# UV-LED.net
KiCad netlist of a schematic drawn in EAGLE
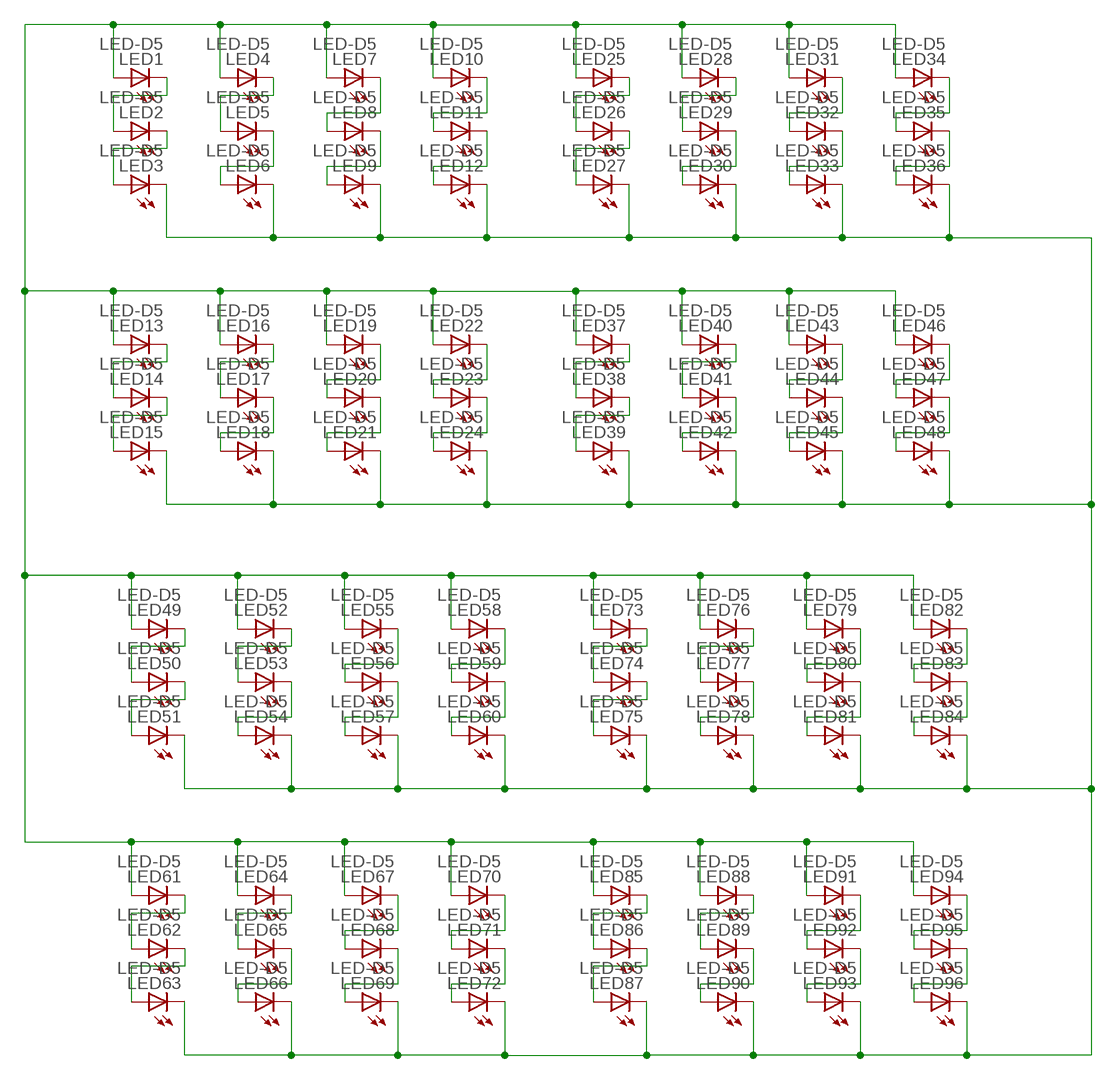
[diagram p0: schematic, sheet 1]

(export (version "E")
  (design (tool "Eeschema 10.0.6"))
  (components
    (comp (ref "LED1")
      (value "LED-D5")
      (footprint "eagle-import:LED-D5")
      (libsource (lib "eagle-import") (part "LED-D5"))
    )
    (comp (ref "LED2")
      (value "LED-D5")
      (footprint "eagle-import:LED-D5")
      (libsource (lib "eagle-import") (part "LED-D5"))
    )
    (comp (ref "LED3")
      (value "LED-D5")
      (footprint "eagle-import:LED-D5")
      (libsource (lib "eagle-import") (part "LED-D5"))
    )
    (comp (ref "LED4")
      (value "LED-D5")
      (footprint "eagle-import:LED-D5")
      (libsource (lib "eagle-import") (part "LED-D5"))
    )
    (comp (ref "LED5")
      (value "LED-D5")
      (footprint "eagle-import:LED-D5")
      (libsource (lib "eagle-import") (part "LED-D5"))
    )
    (comp (ref "LED6")
      (value "LED-D5")
      (footprint "eagle-import:LED-D5")
      (libsource (lib "eagle-import") (part "LED-D5"))
    )
    (comp (ref "LED7")
      (value "LED-D5")
      (footprint "eagle-import:LED-D5")
      (libsource (lib "eagle-import") (part "LED-D5"))
    )
    (comp (ref "LED8")
      (value "LED-D5")
      (footprint "eagle-import:LED-D5")
      (libsource (lib "eagle-import") (part "LED-D5"))
    )
    (comp (ref "LED9")
      (value "LED-D5")
      (footprint "eagle-import:LED-D5")
      (libsource (lib "eagle-import") (part "LED-D5"))
    )
    (comp (ref "LED10")
      (value "LED-D5")
      (footprint "eagle-import:LED-D5")
      (libsource (lib "eagle-import") (part "LED-D5"))
    )
    (comp (ref "LED11")
      (value "LED-D5")
      (footprint "eagle-import:LED-D5")
      (libsource (lib "eagle-import") (part "LED-D5"))
    )
    (comp (ref "LED12")
      (value "LED-D5")
      (footprint "eagle-import:LED-D5")
      (libsource (lib "eagle-import") (part "LED-D5"))
    )
    (comp (ref "LED13")
      (value "LED-D5")
      (footprint "eagle-import:LED-D5")
      (libsource (lib "eagle-import") (part "LED-D5"))
    )
    (comp (ref "LED14")
      (value "LED-D5")
      (footprint "eagle-import:LED-D5")
      (libsource (lib "eagle-import") (part "LED-D5"))
    )
    (comp (ref "LED15")
      (value "LED-D5")
      (footprint "eagle-import:LED-D5")
      (libsource (lib "eagle-import") (part "LED-D5"))
    )
    (comp (ref "LED16")
      (value "LED-D5")
      (footprint "eagle-import:LED-D5")
      (libsource (lib "eagle-import") (part "LED-D5"))
    )
    (comp (ref "LED17")
      (value "LED-D5")
      (footprint "eagle-import:LED-D5")
      (libsource (lib "eagle-import") (part "LED-D5"))
    )
    (comp (ref "LED18")
      (value "LED-D5")
      (footprint "eagle-import:LED-D5")
      (libsource (lib "eagle-import") (part "LED-D5"))
    )
    (comp (ref "LED19")
      (value "LED-D5")
      (footprint "eagle-import:LED-D5")
      (libsource (lib "eagle-import") (part "LED-D5"))
    )
    (comp (ref "LED20")
      (value "LED-D5")
      (footprint "eagle-import:LED-D5")
      (libsource (lib "eagle-import") (part "LED-D5"))
    )
    (comp (ref "LED21")
      (value "LED-D5")
      (footprint "eagle-import:LED-D5")
      (libsource (lib "eagle-import") (part "LED-D5"))
    )
    (comp (ref "LED22")
      (value "LED-D5")
      (footprint "eagle-import:LED-D5")
      (libsource (lib "eagle-import") (part "LED-D5"))
    )
    (comp (ref "LED23")
      (value "LED-D5")
      (footprint "eagle-import:LED-D5")
      (libsource (lib "eagle-import") (part "LED-D5"))
    )
    (comp (ref "LED24")
      (value "LED-D5")
      (footprint "eagle-import:LED-D5")
      (libsource (lib "eagle-import") (part "LED-D5"))
    )
    (comp (ref "LED25")
      (value "LED-D5")
      (footprint "eagle-import:LED-D5")
      (libsource (lib "eagle-import") (part "LED-D5"))
    )
    (comp (ref "LED26")
      (value "LED-D5")
      (footprint "eagle-import:LED-D5")
      (libsource (lib "eagle-import") (part "LED-D5"))
    )
    (comp (ref "LED27")
      (value "LED-D5")
      (footprint "eagle-import:LED-D5")
      (libsource (lib "eagle-import") (part "LED-D5"))
    )
    (comp (ref "LED28")
      (value "LED-D5")
      (footprint "eagle-import:LED-D5")
      (libsource (lib "eagle-import") (part "LED-D5"))
    )
    (comp (ref "LED29")
      (value "LED-D5")
      (footprint "eagle-import:LED-D5")
      (libsource (lib "eagle-import") (part "LED-D5"))
    )
    (comp (ref "LED30")
      (value "LED-D5")
      (footprint "eagle-import:LED-D5")
      (libsource (lib "eagle-import") (part "LED-D5"))
    )
    (comp (ref "LED31")
      (value "LED-D5")
      (footprint "eagle-import:LED-D5")
      (libsource (lib "eagle-import") (part "LED-D5"))
    )
    (comp (ref "LED32")
      (value "LED-D5")
      (footprint "eagle-import:LED-D5")
      (libsource (lib "eagle-import") (part "LED-D5"))
    )
    (comp (ref "LED33")
      (value "LED-D5")
      (footprint "eagle-import:LED-D5")
      (libsource (lib "eagle-import") (part "LED-D5"))
    )
    (comp (ref "LED34")
      (value "LED-D5")
      (footprint "eagle-import:LED-D5")
      (libsource (lib "eagle-import") (part "LED-D5"))
    )
    (comp (ref "LED35")
      (value "LED-D5")
      (footprint "eagle-import:LED-D5")
      (libsource (lib "eagle-import") (part "LED-D5"))
    )
    (comp (ref "LED36")
      (value "LED-D5")
      (footprint "eagle-import:LED-D5")
      (libsource (lib "eagle-import") (part "LED-D5"))
    )
    (comp (ref "LED37")
      (value "LED-D5")
      (footprint "eagle-import:LED-D5")
      (libsource (lib "eagle-import") (part "LED-D5"))
    )
    (comp (ref "LED38")
      (value "LED-D5")
      (footprint "eagle-import:LED-D5")
      (libsource (lib "eagle-import") (part "LED-D5"))
    )
    (comp (ref "LED39")
      (value "LED-D5")
      (footprint "eagle-import:LED-D5")
      (libsource (lib "eagle-import") (part "LED-D5"))
    )
    (comp (ref "LED40")
      (value "LED-D5")
      (footprint "eagle-import:LED-D5")
      (libsource (lib "eagle-import") (part "LED-D5"))
    )
    (comp (ref "LED41")
      (value "LED-D5")
      (footprint "eagle-import:LED-D5")
      (libsource (lib "eagle-import") (part "LED-D5"))
    )
    (comp (ref "LED42")
      (value "LED-D5")
      (footprint "eagle-import:LED-D5")
      (libsource (lib "eagle-import") (part "LED-D5"))
    )
    (comp (ref "LED43")
      (value "LED-D5")
      (footprint "eagle-import:LED-D5")
      (libsource (lib "eagle-import") (part "LED-D5"))
    )
    (comp (ref "LED44")
      (value "LED-D5")
      (footprint "eagle-import:LED-D5")
      (libsource (lib "eagle-import") (part "LED-D5"))
    )
    (comp (ref "LED45")
      (value "LED-D5")
      (footprint "eagle-import:LED-D5")
      (libsource (lib "eagle-import") (part "LED-D5"))
    )
    (comp (ref "LED46")
      (value "LED-D5")
      (footprint "eagle-import:LED-D5")
      (libsource (lib "eagle-import") (part "LED-D5"))
    )
    (comp (ref "LED47")
      (value "LED-D5")
      (footprint "eagle-import:LED-D5")
      (libsource (lib "eagle-import") (part "LED-D5"))
    )
    (comp (ref "LED48")
      (value "LED-D5")
      (footprint "eagle-import:LED-D5")
      (libsource (lib "eagle-import") (part "LED-D5"))
    )
    (comp (ref "LED49")
      (value "LED-D5")
      (footprint "eagle-import:LED-D5")
      (libsource (lib "eagle-import") (part "LED-D5"))
    )
    (comp (ref "LED50")
      (value "LED-D5")
      (footprint "eagle-import:LED-D5")
      (libsource (lib "eagle-import") (part "LED-D5"))
    )
    (comp (ref "LED51")
      (value "LED-D5")
      (footprint "eagle-import:LED-D5")
      (libsource (lib "eagle-import") (part "LED-D5"))
    )
    (comp (ref "LED52")
      (value "LED-D5")
      (footprint "eagle-import:LED-D5")
      (libsource (lib "eagle-import") (part "LED-D5"))
    )
    (comp (ref "LED53")
      (value "LED-D5")
      (footprint "eagle-import:LED-D5")
      (libsource (lib "eagle-import") (part "LED-D5"))
    )
    (comp (ref "LED54")
      (value "LED-D5")
      (footprint "eagle-import:LED-D5")
      (libsource (lib "eagle-import") (part "LED-D5"))
    )
    (comp (ref "LED55")
      (value "LED-D5")
      (footprint "eagle-import:LED-D5")
      (libsource (lib "eagle-import") (part "LED-D5"))
    )
    (comp (ref "LED56")
      (value "LED-D5")
      (footprint "eagle-import:LED-D5")
      (libsource (lib "eagle-import") (part "LED-D5"))
    )
    (comp (ref "LED57")
      (value "LED-D5")
      (footprint "eagle-import:LED-D5")
      (libsource (lib "eagle-import") (part "LED-D5"))
    )
    (comp (ref "LED58")
      (value "LED-D5")
      (footprint "eagle-import:LED-D5")
      (libsource (lib "eagle-import") (part "LED-D5"))
    )
    (comp (ref "LED59")
      (value "LED-D5")
      (footprint "eagle-import:LED-D5")
      (libsource (lib "eagle-import") (part "LED-D5"))
    )
    (comp (ref "LED60")
      (value "LED-D5")
      (footprint "eagle-import:LED-D5")
      (libsource (lib "eagle-import") (part "LED-D5"))
    )
    (comp (ref "LED61")
      (value "LED-D5")
      (footprint "eagle-import:LED-D5")
      (libsource (lib "eagle-import") (part "LED-D5"))
    )
    (comp (ref "LED62")
      (value "LED-D5")
      (footprint "eagle-import:LED-D5")
      (libsource (lib "eagle-import") (part "LED-D5"))
    )
    (comp (ref "LED63")
      (value "LED-D5")
      (footprint "eagle-import:LED-D5")
      (libsource (lib "eagle-import") (part "LED-D5"))
    )
    (comp (ref "LED64")
      (value "LED-D5")
      (footprint "eagle-import:LED-D5")
      (libsource (lib "eagle-import") (part "LED-D5"))
    )
    (comp (ref "LED65")
      (value "LED-D5")
      (footprint "eagle-import:LED-D5")
      (libsource (lib "eagle-import") (part "LED-D5"))
    )
    (comp (ref "LED66")
      (value "LED-D5")
      (footprint "eagle-import:LED-D5")
      (libsource (lib "eagle-import") (part "LED-D5"))
    )
    (comp (ref "LED67")
      (value "LED-D5")
      (footprint "eagle-import:LED-D5")
      (libsource (lib "eagle-import") (part "LED-D5"))
    )
    (comp (ref "LED68")
      (value "LED-D5")
      (footprint "eagle-import:LED-D5")
      (libsource (lib "eagle-import") (part "LED-D5"))
    )
    (comp (ref "LED69")
      (value "LED-D5")
      (footprint "eagle-import:LED-D5")
      (libsource (lib "eagle-import") (part "LED-D5"))
    )
    (comp (ref "LED70")
      (value "LED-D5")
      (footprint "eagle-import:LED-D5")
      (libsource (lib "eagle-import") (part "LED-D5"))
    )
    (comp (ref "LED71")
      (value "LED-D5")
      (footprint "eagle-import:LED-D5")
      (libsource (lib "eagle-import") (part "LED-D5"))
    )
    (comp (ref "LED72")
      (value "LED-D5")
      (footprint "eagle-import:LED-D5")
      (libsource (lib "eagle-import") (part "LED-D5"))
    )
    (comp (ref "LED73")
      (value "LED-D5")
      (footprint "eagle-import:LED-D5")
      (libsource (lib "eagle-import") (part "LED-D5"))
    )
    (comp (ref "LED74")
      (value "LED-D5")
      (footprint "eagle-import:LED-D5")
      (libsource (lib "eagle-import") (part "LED-D5"))
    )
    (comp (ref "LED75")
      (value "LED-D5")
      (footprint "eagle-import:LED-D5")
      (libsource (lib "eagle-import") (part "LED-D5"))
    )
    (comp (ref "LED76")
      (value "LED-D5")
      (footprint "eagle-import:LED-D5")
      (libsource (lib "eagle-import") (part "LED-D5"))
    )
    (comp (ref "LED77")
      (value "LED-D5")
      (footprint "eagle-import:LED-D5")
      (libsource (lib "eagle-import") (part "LED-D5"))
    )
    (comp (ref "LED78")
      (value "LED-D5")
      (footprint "eagle-import:LED-D5")
      (libsource (lib "eagle-import") (part "LED-D5"))
    )
    (comp (ref "LED79")
      (value "LED-D5")
      (footprint "eagle-import:LED-D5")
      (libsource (lib "eagle-import") (part "LED-D5"))
    )
    (comp (ref "LED80")
      (value "LED-D5")
      (footprint "eagle-import:LED-D5")
      (libsource (lib "eagle-import") (part "LED-D5"))
    )
    (comp (ref "LED81")
      (value "LED-D5")
      (footprint "eagle-import:LED-D5")
      (libsource (lib "eagle-import") (part "LED-D5"))
    )
    (comp (ref "LED82")
      (value "LED-D5")
      (footprint "eagle-import:LED-D5")
      (libsource (lib "eagle-import") (part "LED-D5"))
    )
    (comp (ref "LED83")
      (value "LED-D5")
      (footprint "eagle-import:LED-D5")
      (libsource (lib "eagle-import") (part "LED-D5"))
    )
    (comp (ref "LED84")
      (value "LED-D5")
      (footprint "eagle-import:LED-D5")
      (libsource (lib "eagle-import") (part "LED-D5"))
    )
    (comp (ref "LED85")
      (value "LED-D5")
      (footprint "eagle-import:LED-D5")
      (libsource (lib "eagle-import") (part "LED-D5"))
    )
    (comp (ref "LED86")
      (value "LED-D5")
      (footprint "eagle-import:LED-D5")
      (libsource (lib "eagle-import") (part "LED-D5"))
    )
    (comp (ref "LED87")
      (value "LED-D5")
      (footprint "eagle-import:LED-D5")
      (libsource (lib "eagle-import") (part "LED-D5"))
    )
    (comp (ref "LED88")
      (value "LED-D5")
      (footprint "eagle-import:LED-D5")
      (libsource (lib "eagle-import") (part "LED-D5"))
    )
    (comp (ref "LED89")
      (value "LED-D5")
      (footprint "eagle-import:LED-D5")
      (libsource (lib "eagle-import") (part "LED-D5"))
    )
    (comp (ref "LED90")
      (value "LED-D5")
      (footprint "eagle-import:LED-D5")
      (libsource (lib "eagle-import") (part "LED-D5"))
    )
    (comp (ref "LED91")
      (value "LED-D5")
      (footprint "eagle-import:LED-D5")
      (libsource (lib "eagle-import") (part "LED-D5"))
    )
    (comp (ref "LED92")
      (value "LED-D5")
      (footprint "eagle-import:LED-D5")
      (libsource (lib "eagle-import") (part "LED-D5"))
    )
    (comp (ref "LED93")
      (value "LED-D5")
      (footprint "eagle-import:LED-D5")
      (libsource (lib "eagle-import") (part "LED-D5"))
    )
    (comp (ref "LED94")
      (value "LED-D5")
      (footprint "eagle-import:LED-D5")
      (libsource (lib "eagle-import") (part "LED-D5"))
    )
    (comp (ref "LED95")
      (value "LED-D5")
      (footprint "eagle-import:LED-D5")
      (libsource (lib "eagle-import") (part "LED-D5"))
    )
    (comp (ref "LED96")
      (value "LED-D5")
      (footprint "eagle-import:LED-D5")
      (libsource (lib "eagle-import") (part "LED-D5"))
    )
  )
  (nets
    (net (code "1") (name "Net-(LED1-PadA)") (class "Default")
      (node (ref "LED1") (pin "A") (pinfunction "A_A") (pintype "passive"))
      (node (ref "LED10") (pin "A") (pinfunction "A_A") (pintype "passive"))
      (node (ref "LED13") (pin "A") (pinfunction "A_A") (pintype "passive"))
      (node (ref "LED16") (pin "A") (pinfunction "A_A") (pintype "passive"))
      (node (ref "LED19") (pin "A") (pinfunction "A_A") (pintype "passive"))
      (node (ref "LED22") (pin "A") (pinfunction "A_A") (pintype "passive"))
      (node (ref "LED25") (pin "A") (pinfunction "A_A") (pintype "passive"))
      (node (ref "LED28") (pin "A") (pinfunction "A_A") (pintype "passive"))
      (node (ref "LED31") (pin "A") (pinfunction "A_A") (pintype "passive"))
      (node (ref "LED34") (pin "A") (pinfunction "A_A") (pintype "passive"))
      (node (ref "LED37") (pin "A") (pinfunction "A_A") (pintype "passive"))
      (node (ref "LED4") (pin "A") (pinfunction "A_A") (pintype "passive"))
      (node (ref "LED40") (pin "A") (pinfunction "A_A") (pintype "passive"))
      (node (ref "LED43") (pin "A") (pinfunction "A_A") (pintype "passive"))
      (node (ref "LED46") (pin "A") (pinfunction "A_A") (pintype "passive"))
      (node (ref "LED49") (pin "A") (pinfunction "A_A") (pintype "passive"))
      (node (ref "LED52") (pin "A") (pinfunction "A_A") (pintype "passive"))
      (node (ref "LED55") (pin "A") (pinfunction "A_A") (pintype "passive"))
      (node (ref "LED58") (pin "A") (pinfunction "A_A") (pintype "passive"))
      (node (ref "LED61") (pin "A") (pinfunction "A_A") (pintype "passive"))
      (node (ref "LED64") (pin "A") (pinfunction "A_A") (pintype "passive"))
      (node (ref "LED67") (pin "A") (pinfunction "A_A") (pintype "passive"))
      (node (ref "LED7") (pin "A") (pinfunction "A_A") (pintype "passive"))
      (node (ref "LED70") (pin "A") (pinfunction "A_A") (pintype "passive"))
      (node (ref "LED73") (pin "A") (pinfunction "A_A") (pintype "passive"))
      (node (ref "LED76") (pin "A") (pinfunction "A_A") (pintype "passive"))
      (node (ref "LED79") (pin "A") (pinfunction "A_A") (pintype "passive"))
      (node (ref "LED82") (pin "A") (pinfunction "A_A") (pintype "passive"))
      (node (ref "LED85") (pin "A") (pinfunction "A_A") (pintype "passive"))
      (node (ref "LED88") (pin "A") (pinfunction "A_A") (pintype "passive"))
      (node (ref "LED91") (pin "A") (pinfunction "A_A") (pintype "passive"))
      (node (ref "LED94") (pin "A") (pinfunction "A_A") (pintype "passive"))
    )
    (net (code "2") (name "Net-(LED1-PadC)") (class "Default")
      (node (ref "LED1") (pin "C") (pinfunction "C_C") (pintype "passive"))
      (node (ref "LED2") (pin "A") (pinfunction "A_A") (pintype "passive"))
    )
    (net (code "3") (name "Net-(LED2-PadC)") (class "Default")
      (node (ref "LED2") (pin "C") (pinfunction "C_C") (pintype "passive"))
      (node (ref "LED3") (pin "A") (pinfunction "A_A") (pintype "passive"))
    )
    (net (code "4") (name "Net-(LED4-PadC)") (class "Default")
      (node (ref "LED4") (pin "C") (pinfunction "C_C") (pintype "passive"))
      (node (ref "LED5") (pin "A") (pinfunction "A_A") (pintype "passive"))
    )
    (net (code "5") (name "Net-(LED5-PadC)") (class "Default")
      (node (ref "LED5") (pin "C") (pinfunction "C_C") (pintype "passive"))
      (node (ref "LED6") (pin "A") (pinfunction "A_A") (pintype "passive"))
    )
    (net (code "6") (name "Net-(LED7-PadC)") (class "Default")
      (node (ref "LED7") (pin "C") (pinfunction "C_C") (pintype "passive"))
      (node (ref "LED8") (pin "A") (pinfunction "A_A") (pintype "passive"))
    )
    (net (code "7") (name "Net-(LED8-PadC)") (class "Default")
      (node (ref "LED8") (pin "C") (pinfunction "C_C") (pintype "passive"))
      (node (ref "LED9") (pin "A") (pinfunction "A_A") (pintype "passive"))
    )
    (net (code "8") (name "Net-(LED10-PadC)") (class "Default")
      (node (ref "LED10") (pin "C") (pinfunction "C_C") (pintype "passive"))
      (node (ref "LED11") (pin "A") (pinfunction "A_A") (pintype "passive"))
    )
    (net (code "9") (name "Net-(LED11-PadC)") (class "Default")
      (node (ref "LED11") (pin "C") (pinfunction "C_C") (pintype "passive"))
      (node (ref "LED12") (pin "A") (pinfunction "A_A") (pintype "passive"))
    )
    (net (code "10") (name "Net-(LED12-PadC)") (class "Default")
      (node (ref "LED12") (pin "C") (pinfunction "C_C") (pintype "passive"))
      (node (ref "LED15") (pin "C") (pinfunction "C_C") (pintype "passive"))
      (node (ref "LED18") (pin "C") (pinfunction "C_C") (pintype "passive"))
      (node (ref "LED21") (pin "C") (pinfunction "C_C") (pintype "passive"))
      (node (ref "LED24") (pin "C") (pinfunction "C_C") (pintype "passive"))
      (node (ref "LED27") (pin "C") (pinfunction "C_C") (pintype "passive"))
      (node (ref "LED3") (pin "C") (pinfunction "C_C") (pintype "passive"))
      (node (ref "LED30") (pin "C") (pinfunction "C_C") (pintype "passive"))
      (node (ref "LED33") (pin "C") (pinfunction "C_C") (pintype "passive"))
      (node (ref "LED36") (pin "C") (pinfunction "C_C") (pintype "passive"))
      (node (ref "LED39") (pin "C") (pinfunction "C_C") (pintype "passive"))
      (node (ref "LED42") (pin "C") (pinfunction "C_C") (pintype "passive"))
      (node (ref "LED45") (pin "C") (pinfunction "C_C") (pintype "passive"))
      (node (ref "LED48") (pin "C") (pinfunction "C_C") (pintype "passive"))
      (node (ref "LED51") (pin "C") (pinfunction "C_C") (pintype "passive"))
      (node (ref "LED54") (pin "C") (pinfunction "C_C") (pintype "passive"))
      (node (ref "LED57") (pin "C") (pinfunction "C_C") (pintype "passive"))
      (node (ref "LED6") (pin "C") (pinfunction "C_C") (pintype "passive"))
      (node (ref "LED60") (pin "C") (pinfunction "C_C") (pintype "passive"))
      (node (ref "LED63") (pin "C") (pinfunction "C_C") (pintype "passive"))
      (node (ref "LED66") (pin "C") (pinfunction "C_C") (pintype "passive"))
      (node (ref "LED69") (pin "C") (pinfunction "C_C") (pintype "passive"))
      (node (ref "LED72") (pin "C") (pinfunction "C_C") (pintype "passive"))
      (node (ref "LED75") (pin "C") (pinfunction "C_C") (pintype "passive"))
      (node (ref "LED78") (pin "C") (pinfunction "C_C") (pintype "passive"))
      (node (ref "LED81") (pin "C") (pinfunction "C_C") (pintype "passive"))
      (node (ref "LED84") (pin "C") (pinfunction "C_C") (pintype "passive"))
      (node (ref "LED87") (pin "C") (pinfunction "C_C") (pintype "passive"))
      (node (ref "LED9") (pin "C") (pinfunction "C_C") (pintype "passive"))
      (node (ref "LED90") (pin "C") (pinfunction "C_C") (pintype "passive"))
      (node (ref "LED93") (pin "C") (pinfunction "C_C") (pintype "passive"))
      (node (ref "LED96") (pin "C") (pinfunction "C_C") (pintype "passive"))
    )
    (net (code "11") (name "Net-(LED13-PadC)") (class "Default")
      (node (ref "LED13") (pin "C") (pinfunction "C_C") (pintype "passive"))
      (node (ref "LED14") (pin "A") (pinfunction "A_A") (pintype "passive"))
    )
    (net (code "12") (name "Net-(LED14-PadC)") (class "Default")
      (node (ref "LED14") (pin "C") (pinfunction "C_C") (pintype "passive"))
      (node (ref "LED15") (pin "A") (pinfunction "A_A") (pintype "passive"))
    )
    (net (code "13") (name "Net-(LED16-PadC)") (class "Default")
      (node (ref "LED16") (pin "C") (pinfunction "C_C") (pintype "passive"))
      (node (ref "LED17") (pin "A") (pinfunction "A_A") (pintype "passive"))
    )
    (net (code "14") (name "Net-(LED17-PadC)") (class "Default")
      (node (ref "LED17") (pin "C") (pinfunction "C_C") (pintype "passive"))
      (node (ref "LED18") (pin "A") (pinfunction "A_A") (pintype "passive"))
    )
    (net (code "15") (name "Net-(LED19-PadC)") (class "Default")
      (node (ref "LED19") (pin "C") (pinfunction "C_C") (pintype "passive"))
      (node (ref "LED20") (pin "A") (pinfunction "A_A") (pintype "passive"))
    )
    (net (code "16") (name "Net-(LED20-PadC)") (class "Default")
      (node (ref "LED20") (pin "C") (pinfunction "C_C") (pintype "passive"))
      (node (ref "LED21") (pin "A") (pinfunction "A_A") (pintype "passive"))
    )
    (net (code "17") (name "Net-(LED22-PadC)") (class "Default")
      (node (ref "LED22") (pin "C") (pinfunction "C_C") (pintype "passive"))
      (node (ref "LED23") (pin "A") (pinfunction "A_A") (pintype "passive"))
    )
    (net (code "18") (name "Net-(LED23-PadC)") (class "Default")
      (node (ref "LED23") (pin "C") (pinfunction "C_C") (pintype "passive"))
      (node (ref "LED24") (pin "A") (pinfunction "A_A") (pintype "passive"))
    )
    (net (code "19") (name "Net-(LED25-PadC)") (class "Default")
      (node (ref "LED25") (pin "C") (pinfunction "C_C") (pintype "passive"))
      (node (ref "LED26") (pin "A") (pinfunction "A_A") (pintype "passive"))
    )
    (net (code "20") (name "Net-(LED26-PadC)") (class "Default")
      (node (ref "LED26") (pin "C") (pinfunction "C_C") (pintype "passive"))
      (node (ref "LED27") (pin "A") (pinfunction "A_A") (pintype "passive"))
    )
    (net (code "21") (name "Net-(LED28-PadC)") (class "Default")
      (node (ref "LED28") (pin "C") (pinfunction "C_C") (pintype "passive"))
      (node (ref "LED29") (pin "A") (pinfunction "A_A") (pintype "passive"))
    )
    (net (code "22") (name "Net-(LED29-PadC)") (class "Default")
      (node (ref "LED29") (pin "C") (pinfunction "C_C") (pintype "passive"))
      (node (ref "LED30") (pin "A") (pinfunction "A_A") (pintype "passive"))
    )
    (net (code "23") (name "Net-(LED31-PadC)") (class "Default")
      (node (ref "LED31") (pin "C") (pinfunction "C_C") (pintype "passive"))
      (node (ref "LED32") (pin "A") (pinfunction "A_A") (pintype "passive"))
    )
    (net (code "24") (name "Net-(LED32-PadC)") (class "Default")
      (node (ref "LED32") (pin "C") (pinfunction "C_C") (pintype "passive"))
      (node (ref "LED33") (pin "A") (pinfunction "A_A") (pintype "passive"))
    )
    (net (code "25") (name "Net-(LED34-PadC)") (class "Default")
      (node (ref "LED34") (pin "C") (pinfunction "C_C") (pintype "passive"))
      (node (ref "LED35") (pin "A") (pinfunction "A_A") (pintype "passive"))
    )
    (net (code "26") (name "Net-(LED35-PadC)") (class "Default")
      (node (ref "LED35") (pin "C") (pinfunction "C_C") (pintype "passive"))
      (node (ref "LED36") (pin "A") (pinfunction "A_A") (pintype "passive"))
    )
    (net (code "27") (name "Net-(LED37-PadC)") (class "Default")
      (node (ref "LED37") (pin "C") (pinfunction "C_C") (pintype "passive"))
      (node (ref "LED38") (pin "A") (pinfunction "A_A") (pintype "passive"))
    )
    (net (code "28") (name "Net-(LED38-PadC)") (class "Default")
      (node (ref "LED38") (pin "C") (pinfunction "C_C") (pintype "passive"))
      (node (ref "LED39") (pin "A") (pinfunction "A_A") (pintype "passive"))
    )
    (net (code "29") (name "Net-(LED40-PadC)") (class "Default")
      (node (ref "LED40") (pin "C") (pinfunction "C_C") (pintype "passive"))
      (node (ref "LED41") (pin "A") (pinfunction "A_A") (pintype "passive"))
    )
    (net (code "30") (name "Net-(LED41-PadC)") (class "Default")
      (node (ref "LED41") (pin "C") (pinfunction "C_C") (pintype "passive"))
      (node (ref "LED42") (pin "A") (pinfunction "A_A") (pintype "passive"))
    )
    (net (code "31") (name "Net-(LED43-PadC)") (class "Default")
      (node (ref "LED43") (pin "C") (pinfunction "C_C") (pintype "passive"))
      (node (ref "LED44") (pin "A") (pinfunction "A_A") (pintype "passive"))
    )
    (net (code "32") (name "Net-(LED44-PadC)") (class "Default")
      (node (ref "LED44") (pin "C") (pinfunction "C_C") (pintype "passive"))
      (node (ref "LED45") (pin "A") (pinfunction "A_A") (pintype "passive"))
    )
    (net (code "33") (name "Net-(LED46-PadC)") (class "Default")
      (node (ref "LED46") (pin "C") (pinfunction "C_C") (pintype "passive"))
      (node (ref "LED47") (pin "A") (pinfunction "A_A") (pintype "passive"))
    )
    (net (code "34") (name "Net-(LED47-PadC)") (class "Default")
      (node (ref "LED47") (pin "C") (pinfunction "C_C") (pintype "passive"))
      (node (ref "LED48") (pin "A") (pinfunction "A_A") (pintype "passive"))
    )
    (net (code "35") (name "Net-(LED49-PadC)") (class "Default")
      (node (ref "LED49") (pin "C") (pinfunction "C_C") (pintype "passive"))
      (node (ref "LED50") (pin "A") (pinfunction "A_A") (pintype "passive"))
    )
    (net (code "36") (name "Net-(LED50-PadC)") (class "Default")
      (node (ref "LED50") (pin "C") (pinfunction "C_C") (pintype "passive"))
      (node (ref "LED51") (pin "A") (pinfunction "A_A") (pintype "passive"))
    )
    (net (code "37") (name "Net-(LED52-PadC)") (class "Default")
      (node (ref "LED52") (pin "C") (pinfunction "C_C") (pintype "passive"))
      (node (ref "LED53") (pin "A") (pinfunction "A_A") (pintype "passive"))
    )
    (net (code "38") (name "Net-(LED53-PadC)") (class "Default")
      (node (ref "LED53") (pin "C") (pinfunction "C_C") (pintype "passive"))
      (node (ref "LED54") (pin "A") (pinfunction "A_A") (pintype "passive"))
    )
    (net (code "39") (name "Net-(LED55-PadC)") (class "Default")
      (node (ref "LED55") (pin "C") (pinfunction "C_C") (pintype "passive"))
      (node (ref "LED56") (pin "A") (pinfunction "A_A") (pintype "passive"))
    )
    (net (code "40") (name "Net-(LED56-PadC)") (class "Default")
      (node (ref "LED56") (pin "C") (pinfunction "C_C") (pintype "passive"))
      (node (ref "LED57") (pin "A") (pinfunction "A_A") (pintype "passive"))
    )
    (net (code "41") (name "Net-(LED58-PadC)") (class "Default")
      (node (ref "LED58") (pin "C") (pinfunction "C_C") (pintype "passive"))
      (node (ref "LED59") (pin "A") (pinfunction "A_A") (pintype "passive"))
    )
    (net (code "42") (name "Net-(LED59-PadC)") (class "Default")
      (node (ref "LED59") (pin "C") (pinfunction "C_C") (pintype "passive"))
      (node (ref "LED60") (pin "A") (pinfunction "A_A") (pintype "passive"))
    )
    (net (code "43") (name "Net-(LED61-PadC)") (class "Default")
      (node (ref "LED61") (pin "C") (pinfunction "C_C") (pintype "passive"))
      (node (ref "LED62") (pin "A") (pinfunction "A_A") (pintype "passive"))
    )
    (net (code "44") (name "Net-(LED62-PadC)") (class "Default")
      (node (ref "LED62") (pin "C") (pinfunction "C_C") (pintype "passive"))
      (node (ref "LED63") (pin "A") (pinfunction "A_A") (pintype "passive"))
    )
    (net (code "45") (name "Net-(LED64-PadC)") (class "Default")
      (node (ref "LED64") (pin "C") (pinfunction "C_C") (pintype "passive"))
      (node (ref "LED65") (pin "A") (pinfunction "A_A") (pintype "passive"))
    )
    (net (code "46") (name "Net-(LED65-PadC)") (class "Default")
      (node (ref "LED65") (pin "C") (pinfunction "C_C") (pintype "passive"))
      (node (ref "LED66") (pin "A") (pinfunction "A_A") (pintype "passive"))
    )
    (net (code "47") (name "Net-(LED67-PadC)") (class "Default")
      (node (ref "LED67") (pin "C") (pinfunction "C_C") (pintype "passive"))
      (node (ref "LED68") (pin "A") (pinfunction "A_A") (pintype "passive"))
    )
    (net (code "48") (name "Net-(LED68-PadC)") (class "Default")
      (node (ref "LED68") (pin "C") (pinfunction "C_C") (pintype "passive"))
      (node (ref "LED69") (pin "A") (pinfunction "A_A") (pintype "passive"))
    )
    (net (code "49") (name "Net-(LED70-PadC)") (class "Default")
      (node (ref "LED70") (pin "C") (pinfunction "C_C") (pintype "passive"))
      (node (ref "LED71") (pin "A") (pinfunction "A_A") (pintype "passive"))
    )
    (net (code "50") (name "Net-(LED71-PadC)") (class "Default")
      (node (ref "LED71") (pin "C") (pinfunction "C_C") (pintype "passive"))
      (node (ref "LED72") (pin "A") (pinfunction "A_A") (pintype "passive"))
    )
    (net (code "51") (name "Net-(LED73-PadC)") (class "Default")
      (node (ref "LED73") (pin "C") (pinfunction "C_C") (pintype "passive"))
      (node (ref "LED74") (pin "A") (pinfunction "A_A") (pintype "passive"))
    )
    (net (code "52") (name "Net-(LED74-PadC)") (class "Default")
      (node (ref "LED74") (pin "C") (pinfunction "C_C") (pintype "passive"))
      (node (ref "LED75") (pin "A") (pinfunction "A_A") (pintype "passive"))
    )
    (net (code "53") (name "Net-(LED76-PadC)") (class "Default")
      (node (ref "LED76") (pin "C") (pinfunction "C_C") (pintype "passive"))
      (node (ref "LED77") (pin "A") (pinfunction "A_A") (pintype "passive"))
    )
    (net (code "54") (name "Net-(LED77-PadC)") (class "Default")
      (node (ref "LED77") (pin "C") (pinfunction "C_C") (pintype "passive"))
      (node (ref "LED78") (pin "A") (pinfunction "A_A") (pintype "passive"))
    )
    (net (code "55") (name "Net-(LED79-PadC)") (class "Default")
      (node (ref "LED79") (pin "C") (pinfunction "C_C") (pintype "passive"))
      (node (ref "LED80") (pin "A") (pinfunction "A_A") (pintype "passive"))
    )
    (net (code "56") (name "Net-(LED80-PadC)") (class "Default")
      (node (ref "LED80") (pin "C") (pinfunction "C_C") (pintype "passive"))
      (node (ref "LED81") (pin "A") (pinfunction "A_A") (pintype "passive"))
    )
    (net (code "57") (name "Net-(LED82-PadC)") (class "Default")
      (node (ref "LED82") (pin "C") (pinfunction "C_C") (pintype "passive"))
      (node (ref "LED83") (pin "A") (pinfunction "A_A") (pintype "passive"))
    )
    (net (code "58") (name "Net-(LED83-PadC)") (class "Default")
      (node (ref "LED83") (pin "C") (pinfunction "C_C") (pintype "passive"))
      (node (ref "LED84") (pin "A") (pinfunction "A_A") (pintype "passive"))
    )
    (net (code "59") (name "Net-(LED85-PadC)") (class "Default")
      (node (ref "LED85") (pin "C") (pinfunction "C_C") (pintype "passive"))
      (node (ref "LED86") (pin "A") (pinfunction "A_A") (pintype "passive"))
    )
    (net (code "60") (name "Net-(LED86-PadC)") (class "Default")
      (node (ref "LED86") (pin "C") (pinfunction "C_C") (pintype "passive"))
      (node (ref "LED87") (pin "A") (pinfunction "A_A") (pintype "passive"))
    )
    (net (code "61") (name "Net-(LED88-PadC)") (class "Default")
      (node (ref "LED88") (pin "C") (pinfunction "C_C") (pintype "passive"))
      (node (ref "LED89") (pin "A") (pinfunction "A_A") (pintype "passive"))
    )
    (net (code "62") (name "Net-(LED89-PadC)") (class "Default")
      (node (ref "LED89") (pin "C") (pinfunction "C_C") (pintype "passive"))
      (node (ref "LED90") (pin "A") (pinfunction "A_A") (pintype "passive"))
    )
    (net (code "63") (name "Net-(LED91-PadC)") (class "Default")
      (node (ref "LED91") (pin "C") (pinfunction "C_C") (pintype "passive"))
      (node (ref "LED92") (pin "A") (pinfunction "A_A") (pintype "passive"))
    )
    (net (code "64") (name "Net-(LED92-PadC)") (class "Default")
      (node (ref "LED92") (pin "C") (pinfunction "C_C") (pintype "passive"))
      (node (ref "LED93") (pin "A") (pinfunction "A_A") (pintype "passive"))
    )
    (net (code "65") (name "Net-(LED94-PadC)") (class "Default")
      (node (ref "LED94") (pin "C") (pinfunction "C_C") (pintype "passive"))
      (node (ref "LED95") (pin "A") (pinfunction "A_A") (pintype "passive"))
    )
    (net (code "66") (name "Net-(LED95-PadC)") (class "Default")
      (node (ref "LED95") (pin "C") (pinfunction "C_C") (pintype "passive"))
      (node (ref "LED96") (pin "A") (pinfunction "A_A") (pintype "passive"))
    )
  )
)
